# smartstand-led-brightness-evaluation-rev.net
KiCad netlist of a schematic drawn in EAGLE
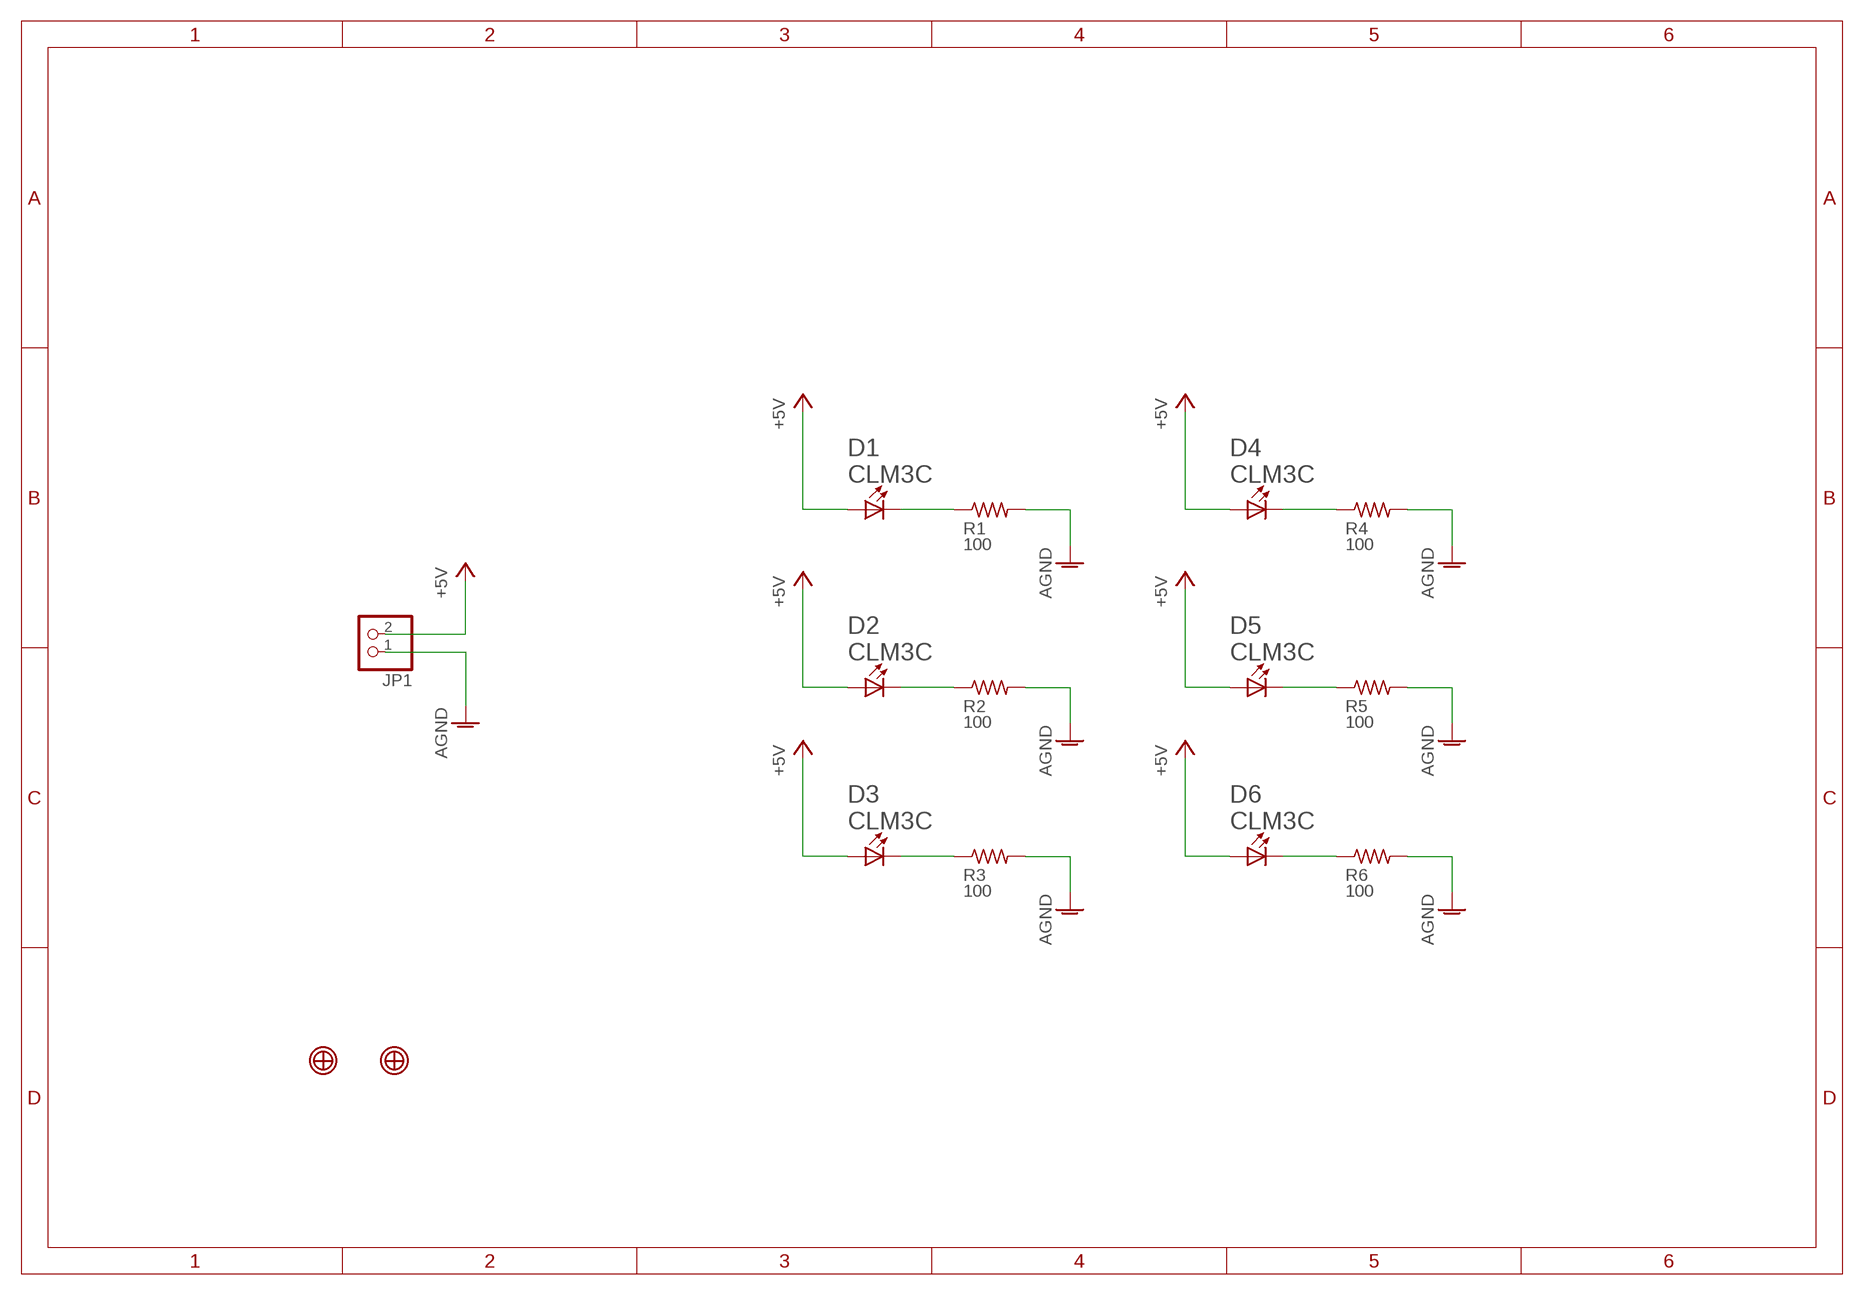
[diagram p0: schematic, sheet 1]

(export (version "E")
  (design (tool "Eeschema 10.0.6"))
  (components
    (comp (ref "D1")
      (value "CLM3C")
      (footprint "eagle-import:PLCC-2")
      (libsource (lib "eagle-import") (part "CLM3C"))
    )
    (comp (ref "D2")
      (value "CLM3C")
      (footprint "eagle-import:PLCC-2")
      (libsource (lib "eagle-import") (part "CLM3C"))
    )
    (comp (ref "D3")
      (value "CLM3C")
      (footprint "eagle-import:PLCC-2")
      (libsource (lib "eagle-import") (part "CLM3C"))
    )
    (comp (ref "D4")
      (value "CLM3C")
      (footprint "eagle-import:PLCC-2")
      (libsource (lib "eagle-import") (part "CLM3C"))
    )
    (comp (ref "D5")
      (value "CLM3C")
      (footprint "eagle-import:PLCC-2")
      (libsource (lib "eagle-import") (part "CLM3C"))
    )
    (comp (ref "D6")
      (value "CLM3C")
      (footprint "eagle-import:PLCC-2")
      (libsource (lib "eagle-import") (part "CLM3C"))
    )
    (comp (ref "JP1")
      (value "PINHD-1X2")
      (footprint "eagle-import:1X02")
      (libsource (lib "eagle-import") (part "PINHD-1X2"))
    )
    (comp (ref "R1")
      (value "100")
      (footprint "eagle-import:R0805")
      (libsource (lib "eagle-import") (part "RESISTOR-HORIZONTAL-0805"))
    )
    (comp (ref "R2")
      (value "100")
      (footprint "eagle-import:R0805")
      (libsource (lib "eagle-import") (part "RESISTOR-HORIZONTAL-0805"))
    )
    (comp (ref "R3")
      (value "100")
      (footprint "eagle-import:R0805")
      (libsource (lib "eagle-import") (part "RESISTOR-HORIZONTAL-0805"))
    )
    (comp (ref "R4")
      (value "100")
      (footprint "eagle-import:R0805")
      (libsource (lib "eagle-import") (part "RESISTOR-HORIZONTAL-0805"))
    )
    (comp (ref "R5")
      (value "100")
      (footprint "eagle-import:R0805")
      (libsource (lib "eagle-import") (part "RESISTOR-HORIZONTAL-0805"))
    )
    (comp (ref "R6")
      (value "100")
      (footprint "eagle-import:R0805")
      (libsource (lib "eagle-import") (part "RESISTOR-HORIZONTAL-0805"))
    )
    (comp (ref "U$1")
      (value "FIDUCIAL-1MM")
      (footprint "eagle-import:FIDUCIAL_1MM")
      (libsource (lib "eagle-import") (part "FIDUCIAL-1MM"))
    )
    (comp (ref "U$2")
      (value "FIDUCIAL-1MM")
      (footprint "eagle-import:FIDUCIAL_1MM")
      (libsource (lib "eagle-import") (part "FIDUCIAL-1MM"))
    )
  )
  (nets
    (net (code "1") (name "+5V") (class "Default")
      (node (ref "D1") (pin "ANODE") (pinfunction "A_ANODE") (pintype "passive"))
      (node (ref "D2") (pin "ANODE") (pinfunction "A_ANODE") (pintype "passive"))
      (node (ref "D3") (pin "ANODE") (pinfunction "A_ANODE") (pintype "passive"))
      (node (ref "D4") (pin "ANODE") (pinfunction "A_ANODE") (pintype "passive"))
      (node (ref "D5") (pin "ANODE") (pinfunction "A_ANODE") (pintype "passive"))
      (node (ref "D6") (pin "ANODE") (pinfunction "A_ANODE") (pintype "passive"))
      (node (ref "JP1") (pin "2") (pinfunction "2_2") (pintype "passive"))
    )
    (net (code "2") (name "AGND") (class "Default")
      (node (ref "JP1") (pin "1") (pinfunction "1_1") (pintype "passive"))
      (node (ref "R1") (pin "2") (pinfunction "2_2") (pintype "passive"))
      (node (ref "R2") (pin "2") (pinfunction "2_2") (pintype "passive"))
      (node (ref "R3") (pin "2") (pinfunction "2_2") (pintype "passive"))
      (node (ref "R4") (pin "2") (pinfunction "2_2") (pintype "passive"))
      (node (ref "R5") (pin "2") (pinfunction "2_2") (pintype "passive"))
      (node (ref "R6") (pin "2") (pinfunction "2_2") (pintype "passive"))
    )
    (net (code "3") (name "Net-(D1-C)") (class "Default")
      (node (ref "D1") (pin "CATHODE") (pinfunction "C_CATHODE") (pintype "passive"))
      (node (ref "R1") (pin "1") (pinfunction "1_1") (pintype "passive"))
    )
    (net (code "4") (name "Net-(D2-C)") (class "Default")
      (node (ref "D2") (pin "CATHODE") (pinfunction "C_CATHODE") (pintype "passive"))
      (node (ref "R2") (pin "1") (pinfunction "1_1") (pintype "passive"))
    )
    (net (code "5") (name "Net-(D3-C)") (class "Default")
      (node (ref "D3") (pin "CATHODE") (pinfunction "C_CATHODE") (pintype "passive"))
      (node (ref "R3") (pin "1") (pinfunction "1_1") (pintype "passive"))
    )
    (net (code "6") (name "Net-(D4-C)") (class "Default")
      (node (ref "D4") (pin "CATHODE") (pinfunction "C_CATHODE") (pintype "passive"))
      (node (ref "R4") (pin "1") (pinfunction "1_1") (pintype "passive"))
    )
    (net (code "7") (name "Net-(D5-C)") (class "Default")
      (node (ref "D5") (pin "CATHODE") (pinfunction "C_CATHODE") (pintype "passive"))
      (node (ref "R5") (pin "1") (pinfunction "1_1") (pintype "passive"))
    )
    (net (code "8") (name "Net-(D6-C)") (class "Default")
      (node (ref "D6") (pin "CATHODE") (pinfunction "C_CATHODE") (pintype "passive"))
      (node (ref "R6") (pin "1") (pinfunction "1_1") (pintype "passive"))
    )
  )
)
